# Xonik_Noise_A6_w_logo_v2_1-12v.net
KiCad netlist of a schematic drawn in EAGLE
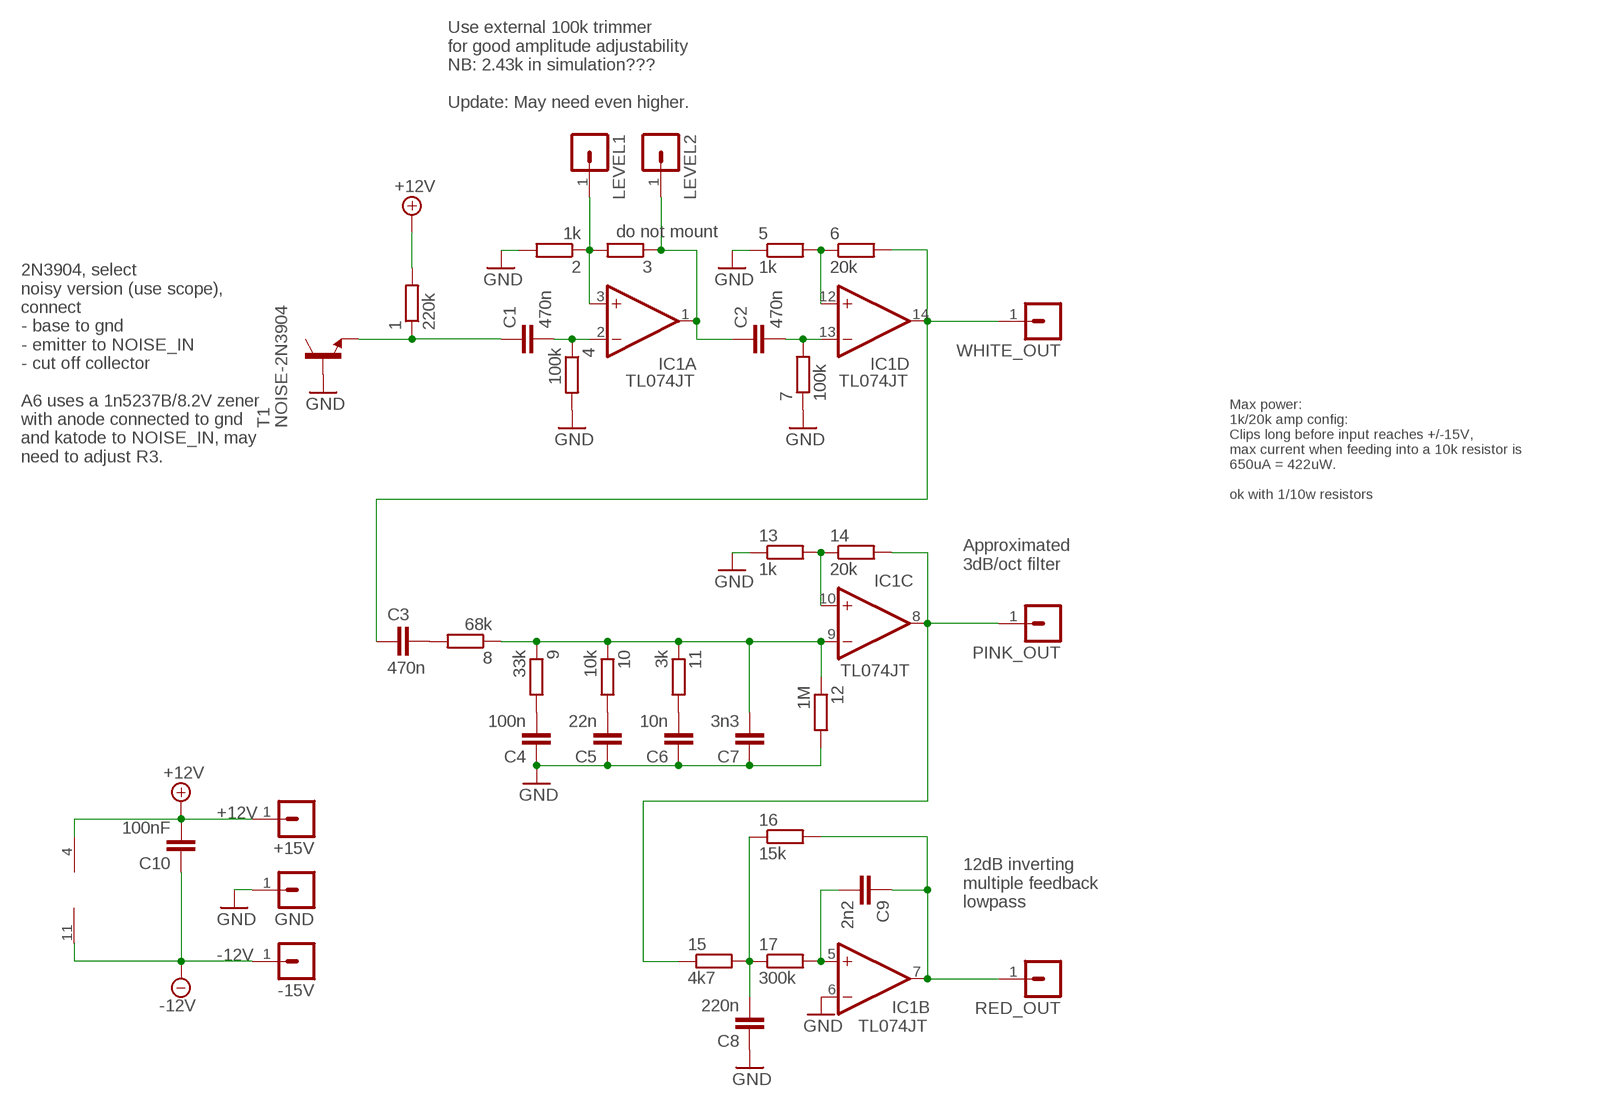
[diagram p0: schematic, sheet 1]

(export (version "E")
  (design (tool "Eeschema 10.0.6"))
  (components
    (comp (ref "+15V")
      (value "MA01-1JP")
      (footprint "eagle-import:SIP-PIN01-1J")
      (libsource (lib "eagle-import") (part "MA01-1JP"))
    )
    (comp (ref "-15V")
      (value "MA01-1JP")
      (footprint "eagle-import:SIP-PIN01-1J")
      (libsource (lib "eagle-import") (part "MA01-1JP"))
    )
    (comp (ref "1")
      (value "220k")
      (footprint "eagle-import:R0603")
      (libsource (lib "eagle-import") (part "R-EU_R0603"))
    )
    (comp (ref "2")
      (value "1k")
      (footprint "eagle-import:R0603")
      (libsource (lib "eagle-import") (part "R-EU_R0603"))
    )
    (comp (ref "3")
      (value "do not mount")
      (footprint "eagle-import:R0603")
      (libsource (lib "eagle-import") (part "R-EU_R0603"))
    )
    (comp (ref "4")
      (value "100k")
      (footprint "eagle-import:R0603")
      (libsource (lib "eagle-import") (part "R-EU_R0603"))
    )
    (comp (ref "5")
      (value "1k")
      (footprint "eagle-import:R0603")
      (libsource (lib "eagle-import") (part "R-EU_R0603"))
    )
    (comp (ref "6")
      (value "20k")
      (footprint "eagle-import:R0603")
      (libsource (lib "eagle-import") (part "R-EU_R0603"))
    )
    (comp (ref "7")
      (value "100k")
      (footprint "eagle-import:R0603")
      (libsource (lib "eagle-import") (part "R-EU_R0603"))
    )
    (comp (ref "8")
      (value "68k")
      (footprint "eagle-import:R0603")
      (libsource (lib "eagle-import") (part "R-EU_R0603"))
    )
    (comp (ref "9")
      (value "33k")
      (footprint "eagle-import:R0603")
      (libsource (lib "eagle-import") (part "R-EU_R0603"))
    )
    (comp (ref "10")
      (value "10k")
      (footprint "eagle-import:R0603")
      (libsource (lib "eagle-import") (part "R-EU_R0603"))
    )
    (comp (ref "11")
      (value "3k")
      (footprint "eagle-import:R0603")
      (libsource (lib "eagle-import") (part "R-EU_R0603"))
    )
    (comp (ref "12")
      (value "1M")
      (footprint "eagle-import:R0603")
      (libsource (lib "eagle-import") (part "R-EU_R0603"))
    )
    (comp (ref "13")
      (value "1k")
      (footprint "eagle-import:R0603")
      (libsource (lib "eagle-import") (part "R-EU_R0603"))
    )
    (comp (ref "14")
      (value "20k")
      (footprint "eagle-import:R0603")
      (libsource (lib "eagle-import") (part "R-EU_R0603"))
    )
    (comp (ref "15")
      (value "4k7")
      (footprint "eagle-import:R0603")
      (libsource (lib "eagle-import") (part "R-EU_R0603"))
    )
    (comp (ref "16")
      (value "15k")
      (footprint "eagle-import:R0603")
      (libsource (lib "eagle-import") (part "R-EU_R0603"))
    )
    (comp (ref "17")
      (value "300k")
      (footprint "eagle-import:R0603")
      (libsource (lib "eagle-import") (part "R-EU_R0603"))
    )
    (comp (ref "C1")
      (value "470n")
      (footprint "eagle-import:C0603")
      (libsource (lib "eagle-import") (part "C-EUC0603"))
    )
    (comp (ref "C2")
      (value "470n")
      (footprint "eagle-import:C0603")
      (libsource (lib "eagle-import") (part "C-EUC0603"))
    )
    (comp (ref "C3")
      (value "470n")
      (footprint "eagle-import:C0603")
      (libsource (lib "eagle-import") (part "C-EUC0603"))
    )
    (comp (ref "C4")
      (value "100n")
      (footprint "eagle-import:C0603")
      (libsource (lib "eagle-import") (part "C-EUC0603"))
    )
    (comp (ref "C5")
      (value "22n")
      (footprint "eagle-import:C0603")
      (libsource (lib "eagle-import") (part "C-EUC0603"))
    )
    (comp (ref "C6")
      (value "10n")
      (footprint "eagle-import:C0603")
      (libsource (lib "eagle-import") (part "C-EUC0603"))
    )
    (comp (ref "C7")
      (value "3n3")
      (footprint "eagle-import:C0603")
      (libsource (lib "eagle-import") (part "C-EUC0603"))
    )
    (comp (ref "C8")
      (value "220n")
      (footprint "eagle-import:C0603")
      (libsource (lib "eagle-import") (part "C-EUC0603"))
    )
    (comp (ref "C9")
      (value "2n2")
      (footprint "eagle-import:C0603")
      (libsource (lib "eagle-import") (part "C-EUC0603"))
    )
    (comp (ref "C10")
      (value "100nF")
      (footprint "eagle-import:C0603")
      (libsource (lib "eagle-import") (part "C-EUC0603"))
    )
    (comp (ref "GND")
      (value "MA01-1JP")
      (footprint "eagle-import:SIP-PIN01-1J")
      (libsource (lib "eagle-import") (part "MA01-1JP"))
    )
    (comp (ref "IC1")
      (value "TL074JT")
      (footprint "eagle-import:TSSOP14J")
      (libsource (lib "eagle-import") (part "TL074JT"))
    )
    (comp (ref "LEVEL1")
      (value "MA01-1JP")
      (footprint "eagle-import:SIP-PIN01-1J")
      (libsource (lib "eagle-import") (part "MA01-1JP"))
    )
    (comp (ref "LEVEL2")
      (value "MA01-1JP")
      (footprint "eagle-import:SIP-PIN01-1J")
      (libsource (lib "eagle-import") (part "MA01-1JP"))
    )
    (comp (ref "PINK_OUT")
      (value "MA01-1JP")
      (footprint "eagle-import:SIP-PIN01-1J")
      (libsource (lib "eagle-import") (part "MA01-1JP"))
    )
    (comp (ref "RED_OUT")
      (value "MA01-1JP")
      (footprint "eagle-import:SIP-PIN01-1J")
      (libsource (lib "eagle-import") (part "MA01-1JP"))
    )
    (comp (ref "T1")
      (value "NOISE-2N3904")
      (footprint "eagle-import:NOISE-2N3904-J")
      (libsource (lib "eagle-import") (part "NOISE-2N3904"))
    )
    (comp (ref "WHITE_OUT")
      (value "MA01-1JP")
      (footprint "eagle-import:SIP-PIN01-1J")
      (libsource (lib "eagle-import") (part "MA01-1JP"))
    )
  )
  (nets
    (net (code "1") (name "+12V") (class "Default")
      (node (ref "+15V") (pin "1") (pinfunction "1_1") (pintype "passive"))
      (node (ref "1") (pin "2") (pinfunction "2_2") (pintype "passive"))
      (node (ref "C10") (pin "2") (pinfunction "2_2") (pintype "passive"))
      (node (ref "IC1") (pin "4") (pinfunction "V+_4") (pintype "power_in"))
    )
    (net (code "2") (name "-12V") (class "Default")
      (node (ref "-15V") (pin "1") (pinfunction "1_1") (pintype "passive"))
      (node (ref "C10") (pin "1") (pinfunction "1_1") (pintype "passive"))
      (node (ref "IC1") (pin "11") (pinfunction "V-_11") (pintype "power_in"))
    )
    (net (code "3") (name "GND") (class "Default")
      (node (ref "12") (pin "2") (pinfunction "2_2") (pintype "passive"))
      (node (ref "13") (pin "1") (pinfunction "1_1") (pintype "passive"))
      (node (ref "2") (pin "2") (pinfunction "2_2") (pintype "passive"))
      (node (ref "4") (pin "2") (pinfunction "2_2") (pintype "passive"))
      (node (ref "5") (pin "1") (pinfunction "1_1") (pintype "passive"))
      (node (ref "7") (pin "1") (pinfunction "1_1") (pintype "passive"))
      (node (ref "C4") (pin "1") (pinfunction "1_1") (pintype "passive"))
      (node (ref "C5") (pin "1") (pinfunction "1_1") (pintype "passive"))
      (node (ref "C6") (pin "1") (pinfunction "1_1") (pintype "passive"))
      (node (ref "C7") (pin "1") (pinfunction "1_1") (pintype "passive"))
      (node (ref "C8") (pin "1") (pinfunction "1_1") (pintype "passive"))
      (node (ref "GND") (pin "1") (pinfunction "1_1") (pintype "passive"))
      (node (ref "IC1") (pin "6") (pinfunction "-IN_6") (pintype "input"))
      (node (ref "T1") (pin "B") (pinfunction "B_B") (pintype "passive"))
    )
    (net (code "4") (name "Net-(1-Pad1)") (class "Default")
      (node (ref "1") (pin "1") (pinfunction "1_1") (pintype "passive"))
      (node (ref "C1") (pin "1") (pinfunction "1_1") (pintype "passive"))
      (node (ref "T1") (pin "E") (pinfunction "E_E") (pintype "passive"))
    )
    (net (code "5") (name "Net-(8-Pad2)") (class "Default")
      (node (ref "8") (pin "2") (pinfunction "2_2") (pintype "passive"))
      (node (ref "C3") (pin "2") (pinfunction "2_2") (pintype "passive"))
    )
    (net (code "6") (name "Net-(9-Pad2)") (class "Default")
      (node (ref "9") (pin "2") (pinfunction "2_2") (pintype "passive"))
      (node (ref "C4") (pin "2") (pinfunction "2_2") (pintype "passive"))
    )
    (net (code "7") (name "Net-(10-Pad2)") (class "Default")
      (node (ref "10") (pin "2") (pinfunction "2_2") (pintype "passive"))
      (node (ref "C5") (pin "2") (pinfunction "2_2") (pintype "passive"))
    )
    (net (code "8") (name "Net-(11-Pad2)") (class "Default")
      (node (ref "11") (pin "2") (pinfunction "2_2") (pintype "passive"))
      (node (ref "C6") (pin "2") (pinfunction "2_2") (pintype "passive"))
    )
    (net (code "9") (name "Net-(15-Pad2)") (class "Default")
      (node (ref "15") (pin "2") (pinfunction "2_2") (pintype "passive"))
      (node (ref "16") (pin "1") (pinfunction "1_1") (pintype "passive"))
      (node (ref "17") (pin "1") (pinfunction "1_1") (pintype "passive"))
      (node (ref "C8") (pin "2") (pinfunction "2_2") (pintype "passive"))
    )
    (net (code "10") (name "Net-(IC1A-+IN)") (class "Default")
      (node (ref "2") (pin "1") (pinfunction "1_1") (pintype "passive"))
      (node (ref "3") (pin "2") (pinfunction "2_2") (pintype "passive"))
      (node (ref "IC1") (pin "3") (pinfunction "+IN_3") (pintype "input"))
      (node (ref "LEVEL1") (pin "1") (pinfunction "1_1") (pintype "passive"))
    )
    (net (code "11") (name "Net-(IC1A--IN)") (class "Default")
      (node (ref "4") (pin "1") (pinfunction "1_1") (pintype "passive"))
      (node (ref "C1") (pin "2") (pinfunction "2_2") (pintype "passive"))
      (node (ref "IC1") (pin "2") (pinfunction "-IN_2") (pintype "input"))
    )
    (net (code "12") (name "Net-(IC1A-OUT)") (class "Default")
      (node (ref "3") (pin "1") (pinfunction "1_1") (pintype "passive"))
      (node (ref "C2") (pin "1") (pinfunction "1_1") (pintype "passive"))
      (node (ref "IC1") (pin "1") (pinfunction "OUT_1") (pintype "output"))
      (node (ref "LEVEL2") (pin "1") (pinfunction "1_1") (pintype "passive"))
    )
    (net (code "13") (name "Net-(IC1B-+IN)") (class "Default")
      (node (ref "17") (pin "2") (pinfunction "2_2") (pintype "passive"))
      (node (ref "C9") (pin "2") (pinfunction "2_2") (pintype "passive"))
      (node (ref "IC1") (pin "5") (pinfunction "+IN_5") (pintype "input"))
    )
    (net (code "14") (name "Net-(IC1B-OUT)") (class "Default")
      (node (ref "16") (pin "2") (pinfunction "2_2") (pintype "passive"))
      (node (ref "C9") (pin "1") (pinfunction "1_1") (pintype "passive"))
      (node (ref "IC1") (pin "7") (pinfunction "OUT_7") (pintype "output"))
      (node (ref "RED_OUT") (pin "1") (pinfunction "1_1") (pintype "passive"))
    )
    (net (code "15") (name "Net-(IC1C-+IN)") (class "Default")
      (node (ref "13") (pin "2") (pinfunction "2_2") (pintype "passive"))
      (node (ref "14") (pin "1") (pinfunction "1_1") (pintype "passive"))
      (node (ref "IC1") (pin "10") (pinfunction "+IN_10") (pintype "input"))
    )
    (net (code "16") (name "Net-(IC1C--IN)") (class "Default")
      (node (ref "10") (pin "1") (pinfunction "1_1") (pintype "passive"))
      (node (ref "11") (pin "1") (pinfunction "1_1") (pintype "passive"))
      (node (ref "12") (pin "1") (pinfunction "1_1") (pintype "passive"))
      (node (ref "8") (pin "1") (pinfunction "1_1") (pintype "passive"))
      (node (ref "9") (pin "1") (pinfunction "1_1") (pintype "passive"))
      (node (ref "C7") (pin "2") (pinfunction "2_2") (pintype "passive"))
      (node (ref "IC1") (pin "9") (pinfunction "-IN_9") (pintype "input"))
    )
    (net (code "17") (name "Net-(IC1C-OUT)") (class "Default")
      (node (ref "14") (pin "2") (pinfunction "2_2") (pintype "passive"))
      (node (ref "15") (pin "1") (pinfunction "1_1") (pintype "passive"))
      (node (ref "IC1") (pin "8") (pinfunction "OUT_8") (pintype "output"))
      (node (ref "PINK_OUT") (pin "1") (pinfunction "1_1") (pintype "passive"))
    )
    (net (code "18") (name "Net-(IC1D-+IN)") (class "Default")
      (node (ref "5") (pin "2") (pinfunction "2_2") (pintype "passive"))
      (node (ref "6") (pin "1") (pinfunction "1_1") (pintype "passive"))
      (node (ref "IC1") (pin "12") (pinfunction "+IN_12") (pintype "input"))
    )
    (net (code "19") (name "Net-(IC1D--IN)") (class "Default")
      (node (ref "7") (pin "2") (pinfunction "2_2") (pintype "passive"))
      (node (ref "C2") (pin "2") (pinfunction "2_2") (pintype "passive"))
      (node (ref "IC1") (pin "13") (pinfunction "-IN_13") (pintype "input"))
    )
    (net (code "20") (name "Net-(IC1D-OUT)") (class "Default")
      (node (ref "6") (pin "2") (pinfunction "2_2") (pintype "passive"))
      (node (ref "C3") (pin "1") (pinfunction "1_1") (pintype "passive"))
      (node (ref "IC1") (pin "14") (pinfunction "OUT_14") (pintype "output"))
      (node (ref "WHITE_OUT") (pin "1") (pinfunction "1_1") (pintype "passive"))
    )
  )
)
